# ADC-RDC-ADC.net
KiCad netlist of a schematic drawn in Altium Designer
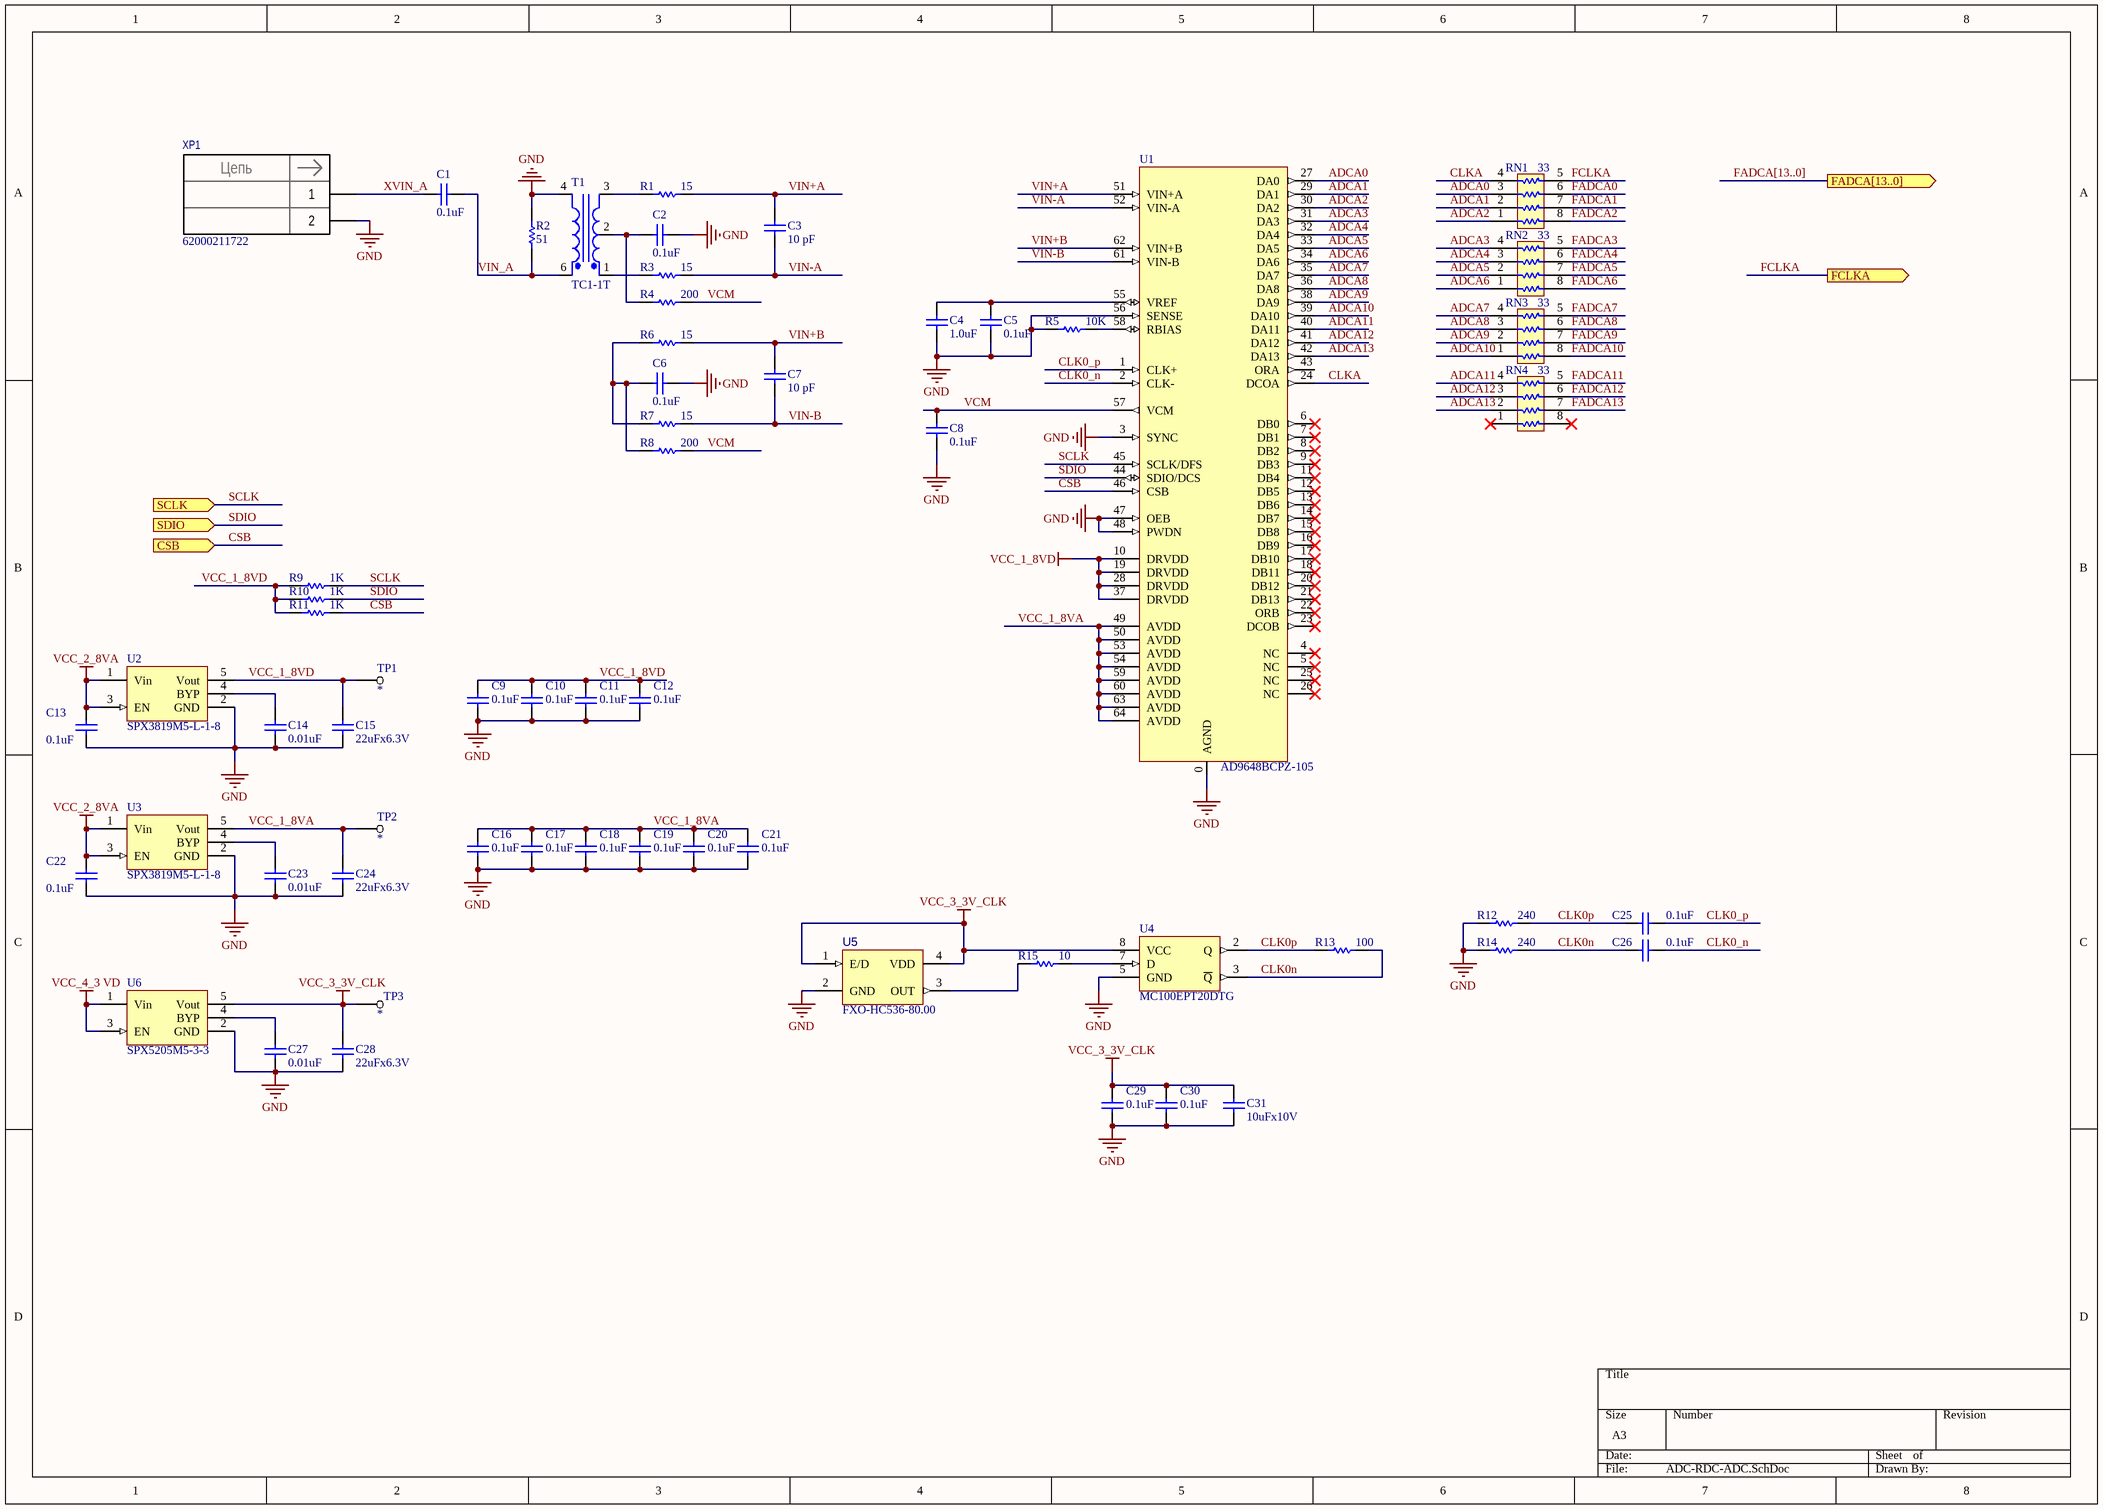
[diagram p0: ADC-RDC-ADC.SchDoc]

(export (version "E")
  (design (tool "Eeschema 10.0.6"))
  (components
    (comp (ref "C1")
      (value "0.1uF")
      (footprint "C0603")
      (description "Capacitor, 2pin")
      (libsource (lib "") (part "Cap_1"))
    )
    (comp (ref "C2")
      (value "0.1uF")
      (footprint "C0603")
      (description "Capacitor, 2pin")
      (libsource (lib "GC500EM2") (part "Cap"))
    )
    (comp (ref "C3")
      (value "10 pF")
      (footprint "C0603")
      (description "Capacitor, 2pin")
      (libsource (lib "GC500EM2") (part "Cap"))
    )
    (comp (ref "C4")
      (value "1.0uF")
      (footprint "C0603L")
      (description "Capacitor, 2pin")
      (libsource (lib "GC500EM2") (part "Cap"))
    )
    (comp (ref "C5")
      (value "0.1uF")
      (footprint "C0603L")
      (description "Capacitor, 2pin")
      (libsource (lib "GC500EM2") (part "Cap"))
    )
    (comp (ref "C6")
      (value "0.1uF")
      (footprint "C0603")
      (description "Capacitor, 2pin")
      (libsource (lib "GC500EM2") (part "Cap"))
    )
    (comp (ref "C7")
      (value "10 pF")
      (footprint "C0603")
      (description "Capacitor, 2pin")
      (libsource (lib "GC500EM2") (part "Cap"))
    )
    (comp (ref "C8")
      (value "0.1uF")
      (footprint "C0603L")
      (description "Capacitor, 2pin")
      (libsource (lib "GC500EM2") (part "Cap"))
    )
    (comp (ref "C9")
      (value "0.1uF")
      (footprint "C0603")
      (description "Capacitor, 2pin")
      (libsource (lib "GC500EM2") (part "Cap"))
    )
    (comp (ref "C10")
      (value "0.1uF")
      (footprint "C0603")
      (description "Capacitor, 2pin")
      (libsource (lib "GC500EM2") (part "Cap"))
    )
    (comp (ref "C11")
      (value "0.1uF")
      (footprint "C0603")
      (description "Capacitor, 2pin")
      (libsource (lib "GC500EM2") (part "Cap"))
    )
    (comp (ref "C12")
      (value "0.1uF")
      (footprint "C0603")
      (description "Capacitor, 2pin")
      (libsource (lib "GC500EM2") (part "Cap"))
    )
    (comp (ref "C13")
      (value "0.1uF")
      (footprint "C0603")
      (description "Capacitor, 2pin")
      (libsource (lib "GC500EM2") (part "Cap"))
    )
    (comp (ref "C14")
      (value "0.01uF")
      (footprint "C0603")
      (description "Capacitor, 2pin")
      (libsource (lib "GC500EM2") (part "Cap"))
    )
    (comp (ref "C15")
      (value "22uFx6.3V")
      (footprint "C0805")
      (description "Capacitor, 2pin")
      (libsource (lib "GC500EM2") (part "Cap"))
    )
    (comp (ref "C16")
      (value "0.1uF")
      (footprint "C0603L")
      (description "Capacitor, 2pin")
      (libsource (lib "GC500EM2") (part "Cap"))
    )
    (comp (ref "C17")
      (value "0.1uF")
      (footprint "C0603L")
      (description "Capacitor, 2pin")
      (libsource (lib "GC500EM2") (part "Cap"))
    )
    (comp (ref "C18")
      (value "0.1uF")
      (footprint "C0603L")
      (description "Capacitor, 2pin")
      (libsource (lib "GC500EM2") (part "Cap"))
    )
    (comp (ref "C19")
      (value "0.1uF")
      (footprint "C0603L")
      (description "Capacitor, 2pin")
      (libsource (lib "GC500EM2") (part "Cap"))
    )
    (comp (ref "C20")
      (value "0.1uF")
      (footprint "C0603L")
      (description "Capacitor, 2pin")
      (libsource (lib "GC500EM2") (part "Cap"))
    )
    (comp (ref "C21")
      (value "0.1uF")
      (footprint "C0603L")
      (description "Capacitor, 2pin")
      (libsource (lib "GC500EM2") (part "Cap"))
    )
    (comp (ref "C22")
      (value "0.1uF")
      (footprint "C0603")
      (description "Capacitor, 2pin")
      (libsource (lib "GC500EM2") (part "Cap"))
    )
    (comp (ref "C23")
      (value "0.01uF")
      (footprint "C0603")
      (description "Capacitor, 2pin")
      (libsource (lib "GC500EM2") (part "Cap"))
    )
    (comp (ref "C24")
      (value "22uFx6.3V")
      (footprint "C0805")
      (description "Capacitor, 2pin")
      (libsource (lib "GC500EM2") (part "Cap"))
    )
    (comp (ref "C25")
      (value "0.1uF")
      (footprint "C0603L")
      (description "Capacitor, 2pin")
      (libsource (lib "GC500EM2") (part "Cap"))
    )
    (comp (ref "C26")
      (value "0.1uF")
      (footprint "C0603L")
      (description "Capacitor, 2pin")
      (libsource (lib "GC500EM2") (part "Cap"))
    )
    (comp (ref "C27")
      (value "0.01uF")
      (footprint "C0603")
      (description "Capacitor, 2pin")
      (libsource (lib "GC500EM2") (part "Cap"))
    )
    (comp (ref "C28")
      (value "22uFx6.3V")
      (footprint "C0805")
      (description "Capacitor, 2pin")
      (libsource (lib "GC500EM2") (part "Cap"))
    )
    (comp (ref "C29")
      (value "0.1uF")
      (footprint "C0603")
      (description "Capacitor, 2pin")
      (libsource (lib "GC500EM2") (part "Cap"))
    )
    (comp (ref "C30")
      (value "0.1uF")
      (footprint "C0603")
      (description "Capacitor, 2pin")
      (libsource (lib "GC500EM2") (part "Cap"))
    )
    (comp (ref "C31")
      (value "10uFx10V")
      (footprint "C0805")
      (description "Capacitor, 2pin")
      (libsource (lib "GC500EM2") (part "Cap"))
    )
    (comp (ref "R1")
      (value "15")
      (footprint "R0603")
      (description "Resistor, 2pin")
      (libsource (lib "GC500EM2") (part "RES"))
    )
    (comp (ref "R2")
      (value "51")
      (footprint "R0805")
      (description "Resistor, 2pin")
      (libsource (lib "GC500EM2") (part "RES"))
    )
    (comp (ref "R3")
      (value "15")
      (footprint "R0603")
      (description "Resistor, 2pin")
      (libsource (lib "GC500EM2") (part "RES"))
    )
    (comp (ref "R4")
      (value "200")
      (footprint "R0603")
      (description "Resistor, 2pin")
      (libsource (lib "GC500EM2") (part "RES"))
    )
    (comp (ref "R5")
      (value "10K")
      (footprint "R0603L")
      (description "Resistor, 2pin")
      (libsource (lib "GC500EM2") (part "RES"))
    )
    (comp (ref "R6")
      (value "15")
      (footprint "R0603")
      (description "Resistor, 2pin")
      (libsource (lib "GC500EM2") (part "RES"))
    )
    (comp (ref "R7")
      (value "15")
      (footprint "R0603")
      (description "Resistor, 2pin")
      (libsource (lib "GC500EM2") (part "RES"))
    )
    (comp (ref "R8")
      (value "200")
      (footprint "R0603")
      (description "Resistor, 2pin")
      (libsource (lib "GC500EM2") (part "RES"))
    )
    (comp (ref "R9")
      (value "1K")
      (footprint "R0603")
      (description "Resistor, 2pin")
      (libsource (lib "GC500EM2") (part "RES"))
    )
    (comp (ref "R10")
      (value "1K")
      (footprint "R0603")
      (description "Resistor, 2pin")
      (libsource (lib "GC500EM2") (part "RES"))
    )
    (comp (ref "R11")
      (value "1K")
      (footprint "R0603")
      (description "Resistor, 2pin")
      (libsource (lib "GC500EM2") (part "RES"))
    )
    (comp (ref "R12")
      (value "240")
      (footprint "R0603")
      (description "Resistor, 2pin")
      (libsource (lib "GC500EM2") (part "RES"))
    )
    (comp (ref "R13")
      (value "100")
      (footprint "R0603")
      (description "Resistor, 2pin")
      (libsource (lib "GC500EM2") (part "RES"))
    )
    (comp (ref "R14")
      (value "240")
      (footprint "R0603")
      (description "Resistor, 2pin")
      (libsource (lib "GC500EM2") (part "RES"))
    )
    (comp (ref "R15")
      (value "10")
      (footprint "R0603")
      (description "Resistor, 2pin")
      (libsource (lib "GC500EM2") (part "RES"))
    )
    (comp (ref "RN1")
      (value "33")
      (footprint "EXB38V")
      (description "x4 Resistor Array")
      (libsource (lib "GC500EM2") (part "x4 Resistor Array"))
    )
    (comp (ref "RN2")
      (value "33")
      (footprint "EXB38V")
      (description "x4 Resistor Array")
      (libsource (lib "GC500EM2") (part "x4 Resistor Array"))
    )
    (comp (ref "RN3")
      (value "33")
      (footprint "EXB38V")
      (description "x4 Resistor Array")
      (libsource (lib "GC500EM2") (part "x4 Resistor Array"))
    )
    (comp (ref "RN4")
      (value "33")
      (footprint "EXB38V")
      (description "x4 Resistor Array")
      (libsource (lib "GC500EM2") (part "x4 Resistor Array"))
    )
    (comp (ref "T1")
      (value "TC1-1T")
      (footprint "SM-22")
      (description "Center-Tapped Transformer (Ideal)")
      (libsource (lib "GC500EM2") (part "TC1-1T"))
    )
    (comp (ref "TP1")
      (value "*")
      (footprint "TP_1_06")
      (description "Test point")
      (libsource (lib "GC500EM2") (part "Test_point"))
    )
    (comp (ref "TP2")
      (value "*")
      (footprint "TP_1_06")
      (description "Test point")
      (libsource (lib "GC500EM2") (part "Test_point"))
    )
    (comp (ref "TP3")
      (value "*")
      (footprint "TP_1_06")
      (description "Test point")
      (libsource (lib "GC500EM2") (part "Test_point"))
    )
    (comp (ref "U1")
      (value "AD9648BCPZ-105")
      (footprint "CP-64-4")
      (description "14-Bit, 125 MSPS/105 MSPS, 1.8 V Dual  Analog-to-Digital Converter")
      (libsource (lib "GC500EM2") (part "AD9648BCPZ-105"))
    )
    (comp (ref "U2")
      (value "SPX3819M5-L-1-8")
      (footprint "SOT23-5")
      (description "LDO Voltage Regulator")
      (libsource (lib "GC500EM2") (part "SPX3819M5-L-1-8"))
    )
    (comp (ref "U3")
      (value "SPX3819M5-L-1-8")
      (footprint "SOT23-5")
      (description "LDO Voltage Regulator")
      (libsource (lib "GC500EM2") (part "SPX3819M5-L-1-8"))
    )
    (comp (ref "U4")
      (value "MC100EPT20DTG")
      (footprint "TSSOP8")
      (description "3.3 V TTL/CMOS to differential PECL translator")
      (libsource (lib "GC500EM2") (part "MC100EPT20DT"))
    )
    (comp (ref "U5")
      (value "FXO-HC536-80.00")
      (footprint "HC5")
      (description "Surface Mount Crystal Oscillator")
      (libsource (lib "GC500EM2") (part "SG-636PTF-40.0000"))
    )
    (comp (ref "U6")
      (value "SPX5205M5-3-3")
      (footprint "SOT23-5")
      (description "LDO Voltage Regulator")
      (libsource (lib "GC500EM2") (part "SPX5205M5-3-3"))
    )
    (comp (ref "XP1")
      (value "plug_62000211722_WR-WTB_2pin_horiz")
      (footprint "conP_WR-WTB_62000211722-2pin_P2000_60x76x48_L")
      (description "2.00mm Male Horizontal Shrouded Header WR-WTB")
      (fields
        (field (name "COMPONENT_NAME") "62000211722")
        (field (name "MANUFACTURER") "\"Wurth Elektronik\"")
      )
      (libsource (lib "Electromechanics") (part "plug_62000211722_WR-WTB_2pin_horiz"))
    )
  )
  (nets
    (net (code "1") (name "/ADCA0") (class "Default")
      (node (ref "RN1") (pin "3") (pintype "passive"))
      (node (ref "U1") (pin "27") (pinfunction "DA0_27") (pintype "output"))
    )
    (net (code "2") (name "/ADCA1") (class "Default")
      (node (ref "RN1") (pin "2") (pintype "passive"))
      (node (ref "U1") (pin "29") (pinfunction "DA1_29") (pintype "output"))
    )
    (net (code "3") (name "/ADCA2") (class "Default")
      (node (ref "RN1") (pin "1") (pintype "passive"))
      (node (ref "U1") (pin "30") (pinfunction "DA2_30") (pintype "output"))
    )
    (net (code "4") (name "/ADCA3") (class "Default")
      (node (ref "RN2") (pin "4") (pintype "passive"))
      (node (ref "U1") (pin "31") (pinfunction "DA3_31") (pintype "output"))
    )
    (net (code "5") (name "/ADCA4") (class "Default")
      (node (ref "RN2") (pin "3") (pintype "passive"))
      (node (ref "U1") (pin "32") (pinfunction "DA4_32") (pintype "output"))
    )
    (net (code "6") (name "/ADCA5") (class "Default")
      (node (ref "RN2") (pin "2") (pintype "passive"))
      (node (ref "U1") (pin "33") (pinfunction "DA5_33") (pintype "output"))
    )
    (net (code "7") (name "/ADCA6") (class "Default")
      (node (ref "RN2") (pin "1") (pintype "passive"))
      (node (ref "U1") (pin "34") (pinfunction "DA6_34") (pintype "output"))
    )
    (net (code "8") (name "/ADCA7") (class "Default")
      (node (ref "RN3") (pin "4") (pintype "passive"))
      (node (ref "U1") (pin "35") (pinfunction "DA7_35") (pintype "output"))
    )
    (net (code "9") (name "/ADCA8") (class "Default")
      (node (ref "RN3") (pin "3") (pintype "passive"))
      (node (ref "U1") (pin "36") (pinfunction "DA8_36") (pintype "output"))
    )
    (net (code "10") (name "/ADCA9") (class "Default")
      (node (ref "RN3") (pin "2") (pintype "passive"))
      (node (ref "U1") (pin "38") (pinfunction "DA9_38") (pintype "output"))
    )
    (net (code "11") (name "/ADCA10") (class "Default")
      (node (ref "RN3") (pin "1") (pintype "passive"))
      (node (ref "U1") (pin "39") (pinfunction "DA10_39") (pintype "output"))
    )
    (net (code "12") (name "/ADCA11") (class "Default")
      (node (ref "RN4") (pin "4") (pintype "passive"))
      (node (ref "U1") (pin "40") (pinfunction "DA11_40") (pintype "output"))
    )
    (net (code "13") (name "/ADCA12") (class "Default")
      (node (ref "RN4") (pin "3") (pintype "passive"))
      (node (ref "U1") (pin "41") (pinfunction "DA12_41") (pintype "output"))
    )
    (net (code "14") (name "/ADCA13") (class "Default")
      (node (ref "RN4") (pin "2") (pintype "passive"))
      (node (ref "U1") (pin "42") (pinfunction "DA13_42") (pintype "output"))
    )
    (net (code "15") (name "/CLK0_n") (class "Default")
      (node (ref "C26") (pin "2") (pinfunction "2_2") (pintype "passive"))
      (node (ref "U1") (pin "2") (pinfunction "CLK-_2") (pintype "input"))
    )
    (net (code "16") (name "/CLK0_p") (class "Default")
      (node (ref "C25") (pin "2") (pinfunction "2_2") (pintype "passive"))
      (node (ref "U1") (pin "1") (pinfunction "CLK+_1") (pintype "input"))
    )
    (net (code "17") (name "/CLK0n") (class "Default")
      (node (ref "C26") (pin "1") (pinfunction "1_1") (pintype "passive"))
      (node (ref "R13") (pin "2") (pinfunction "2_2") (pintype "passive"))
      (node (ref "R14") (pin "2") (pinfunction "2_2") (pintype "passive"))
      (node (ref "U4") (pin "3") (pinfunction "~{Q}_3") (pintype "output"))
    )
    (net (code "18") (name "/CLK0p") (class "Default")
      (node (ref "C25") (pin "1") (pinfunction "1_1") (pintype "passive"))
      (node (ref "R12") (pin "2") (pinfunction "2_2") (pintype "passive"))
      (node (ref "R13") (pin "1") (pinfunction "1_1") (pintype "passive"))
      (node (ref "U4") (pin "2") (pinfunction "Q_2") (pintype "output"))
    )
    (net (code "19") (name "/CLKA") (class "Default")
      (node (ref "RN1") (pin "4") (pintype "passive"))
      (node (ref "U1") (pin "24") (pinfunction "DCOA_24") (pintype "output"))
    )
    (net (code "20") (name "/CSB") (class "Default")
      (node (ref "R11") (pin "2") (pinfunction "2_2") (pintype "passive"))
      (node (ref "U1") (pin "46") (pinfunction "CSB_46") (pintype "input"))
    )
    (net (code "21") (name "/FADCA0") (class "Default") (node (ref "RN1") (pin "6") (pintype "passive")))
    (net (code "22") (name "/FADCA1") (class "Default") (node (ref "RN1") (pin "7") (pintype "passive")))
    (net (code "23") (name "/FADCA2") (class "Default") (node (ref "RN1") (pin "8") (pintype "passive")))
    (net (code "24") (name "/FADCA3") (class "Default") (node (ref "RN2") (pin "5") (pintype "passive")))
    (net (code "25") (name "/FADCA4") (class "Default") (node (ref "RN2") (pin "6") (pintype "passive")))
    (net (code "26") (name "/FADCA5") (class "Default") (node (ref "RN2") (pin "7") (pintype "passive")))
    (net (code "27") (name "/FADCA6") (class "Default") (node (ref "RN2") (pin "8") (pintype "passive")))
    (net (code "28") (name "/FADCA7") (class "Default") (node (ref "RN3") (pin "5") (pintype "passive")))
    (net (code "29") (name "/FADCA8") (class "Default") (node (ref "RN3") (pin "6") (pintype "passive")))
    (net (code "30") (name "/FADCA9") (class "Default") (node (ref "RN3") (pin "7") (pintype "passive")))
    (net (code "31") (name "/FADCA10") (class "Default") (node (ref "RN3") (pin "8") (pintype "passive")))
    (net (code "32") (name "/FADCA11") (class "Default") (node (ref "RN4") (pin "5") (pintype "passive")))
    (net (code "33") (name "/FADCA12") (class "Default") (node (ref "RN4") (pin "6") (pintype "passive")))
    (net (code "34") (name "/FADCA13") (class "Default") (node (ref "RN4") (pin "7") (pintype "passive")))
    (net (code "36") (name "/FCLKA") (class "Default") (node (ref "RN1") (pin "5") (pintype "passive")))
    (net (code "37") (name "/SCLK") (class "Default")
      (node (ref "R9") (pin "2") (pinfunction "2_2") (pintype "passive"))
      (node (ref "U1") (pin "45") (pinfunction "SCLK/DFS_45") (pintype "input"))
    )
    (net (code "38") (name "/SDIO") (class "Default")
      (node (ref "R10") (pin "2") (pinfunction "2_2") (pintype "passive"))
      (node (ref "U1") (pin "44") (pinfunction "SDIO/DCS_44") (pintype "bidirectional"))
    )
    (net (code "39") (name "/VCC_1_8VA") (class "Default")
      (node (ref "C16") (pin "2") (pinfunction "2_2") (pintype "passive"))
      (node (ref "C17") (pin "2") (pinfunction "2_2") (pintype "passive"))
      (node (ref "C18") (pin "2") (pinfunction "2_2") (pintype "passive"))
      (node (ref "C19") (pin "2") (pinfunction "2_2") (pintype "passive"))
      (node (ref "C20") (pin "2") (pinfunction "2_2") (pintype "passive"))
      (node (ref "C21") (pin "2") (pinfunction "2_2") (pintype "passive"))
      (node (ref "C24") (pin "2") (pinfunction "2_2") (pintype "passive"))
      (node (ref "TP2") (pin "1") (pinfunction "1_1") (pintype "passive"))
      (node (ref "U1") (pin "49") (pinfunction "AVDD_49") (pintype "power_in"))
      (node (ref "U1") (pin "50") (pinfunction "AVDD_50") (pintype "power_in"))
      (node (ref "U1") (pin "53") (pinfunction "AVDD_53") (pintype "power_in"))
      (node (ref "U1") (pin "54") (pinfunction "AVDD_54") (pintype "power_in"))
      (node (ref "U1") (pin "59") (pinfunction "AVDD_59") (pintype "power_in"))
      (node (ref "U1") (pin "60") (pinfunction "AVDD_60") (pintype "power_in"))
      (node (ref "U1") (pin "63") (pinfunction "AVDD_63") (pintype "power_in"))
      (node (ref "U1") (pin "64") (pinfunction "AVDD_64") (pintype "power_in"))
      (node (ref "U3") (pin "5") (pinfunction "Vout_5") (pintype "passive"))
    )
    (net (code "40") (name "/VCM") (class "Default")
      (node (ref "C8") (pin "2") (pinfunction "2_2") (pintype "passive"))
      (node (ref "R4") (pin "2") (pinfunction "2_2") (pintype "passive"))
      (node (ref "R8") (pin "2") (pinfunction "2_2") (pintype "passive"))
      (node (ref "U1") (pin "57") (pinfunction "VCM_57") (pintype "output"))
    )
    (net (code "41") (name "/VIN+A") (class "Default")
      (node (ref "C3") (pin "1") (pinfunction "1_1") (pintype "passive"))
      (node (ref "R1") (pin "2") (pinfunction "2_2") (pintype "passive"))
      (node (ref "U1") (pin "51") (pinfunction "VIN+A_51") (pintype "input"))
    )
    (net (code "42") (name "/VIN+B") (class "Default")
      (node (ref "C7") (pin "1") (pinfunction "1_1") (pintype "passive"))
      (node (ref "R6") (pin "2") (pinfunction "2_2") (pintype "passive"))
      (node (ref "U1") (pin "62") (pinfunction "VIN+B_62") (pintype "input"))
    )
    (net (code "43") (name "/VIN-A") (class "Default")
      (node (ref "C3") (pin "2") (pinfunction "2_2") (pintype "passive"))
      (node (ref "R3") (pin "2") (pinfunction "2_2") (pintype "passive"))
      (node (ref "U1") (pin "52") (pinfunction "VIN-A_52") (pintype "input"))
    )
    (net (code "44") (name "/VIN-B") (class "Default")
      (node (ref "C7") (pin "2") (pinfunction "2_2") (pintype "passive"))
      (node (ref "R7") (pin "2") (pinfunction "2_2") (pintype "passive"))
      (node (ref "U1") (pin "61") (pinfunction "VIN-B_61") (pintype "input"))
    )
    (net (code "45") (name "/VIN_A") (class "Default")
      (node (ref "C1") (pin "1") (pinfunction "1_1") (pintype "passive"))
      (node (ref "R2") (pin "1") (pinfunction "1_1") (pintype "passive"))
      (node (ref "T1") (pin "6") (pinfunction "Pri+_6") (pintype "passive"))
    )
    (net (code "46") (name "/XVIN_A") (class "Default")
      (node (ref "C1") (pin "2") (pinfunction "2_2") (pintype "passive"))
      (node (ref "XP1") (pin "1") (pinfunction "1_1") (pintype "passive"))
    )
    (net (code "47") (name "GND") (class "Default")
      (node (ref "C10") (pin "1") (pinfunction "1_1") (pintype "passive"))
      (node (ref "C11") (pin "1") (pinfunction "1_1") (pintype "passive"))
      (node (ref "C12") (pin "1") (pinfunction "1_1") (pintype "passive"))
      (node (ref "C13") (pin "1") (pinfunction "1_1") (pintype "passive"))
      (node (ref "C14") (pin "1") (pinfunction "1_1") (pintype "passive"))
      (node (ref "C15") (pin "1") (pinfunction "1_1") (pintype "passive"))
      (node (ref "C16") (pin "1") (pinfunction "1_1") (pintype "passive"))
      (node (ref "C17") (pin "1") (pinfunction "1_1") (pintype "passive"))
      (node (ref "C18") (pin "1") (pinfunction "1_1") (pintype "passive"))
      (node (ref "C19") (pin "1") (pinfunction "1_1") (pintype "passive"))
      (node (ref "C2") (pin "2") (pinfunction "2_2") (pintype "passive"))
      (node (ref "C20") (pin "1") (pinfunction "1_1") (pintype "passive"))
      (node (ref "C21") (pin "1") (pinfunction "1_1") (pintype "passive"))
      (node (ref "C22") (pin "1") (pinfunction "1_1") (pintype "passive"))
      (node (ref "C23") (pin "1") (pinfunction "1_1") (pintype "passive"))
      (node (ref "C24") (pin "1") (pinfunction "1_1") (pintype "passive"))
      (node (ref "C27") (pin "1") (pinfunction "1_1") (pintype "passive"))
      (node (ref "C28") (pin "1") (pinfunction "1_1") (pintype "passive"))
      (node (ref "C29") (pin "1") (pinfunction "1_1") (pintype "passive"))
      (node (ref "C30") (pin "1") (pinfunction "1_1") (pintype "passive"))
      (node (ref "C31") (pin "1") (pinfunction "1_1") (pintype "passive"))
      (node (ref "C4") (pin "1") (pinfunction "1_1") (pintype "passive"))
      (node (ref "C5") (pin "1") (pinfunction "1_1") (pintype "passive"))
      (node (ref "C6") (pin "2") (pinfunction "2_2") (pintype "passive"))
      (node (ref "C8") (pin "1") (pinfunction "1_1") (pintype "passive"))
      (node (ref "C9") (pin "1") (pinfunction "1_1") (pintype "passive"))
      (node (ref "R12") (pin "1") (pinfunction "1_1") (pintype "passive"))
      (node (ref "R14") (pin "1") (pinfunction "1_1") (pintype "passive"))
      (node (ref "R2") (pin "2") (pinfunction "2_2") (pintype "passive"))
      (node (ref "R5") (pin "1") (pinfunction "1_1") (pintype "passive"))
      (node (ref "T1") (pin "4") (pinfunction "Pri-_4") (pintype "passive"))
      (node (ref "U1") (pin "0") (pinfunction "AGND_0") (pintype "power_in"))
      (node (ref "U1") (pin "3") (pinfunction "SYNC_3") (pintype "input"))
      (node (ref "U1") (pin "47") (pinfunction "OEB_47") (pintype "input"))
      (node (ref "U1") (pin "48") (pinfunction "PWDN_48") (pintype "input"))
      (node (ref "U1") (pin "56") (pinfunction "SENSE_56") (pintype "input"))
      (node (ref "U2") (pin "2") (pinfunction "GND_2") (pintype "passive"))
      (node (ref "U3") (pin "2") (pinfunction "GND_2") (pintype "passive"))
      (node (ref "U4") (pin "5") (pinfunction "GND_5") (pintype "power_in"))
      (node (ref "U5") (pin "2") (pinfunction "GND_2") (pintype "power_in"))
      (node (ref "U6") (pin "2") (pinfunction "GND_2") (pintype "passive"))
      (node (ref "XP1") (pin "2") (pinfunction "2_2") (pintype "passive"))
    )
    (net (code "48") (name "Net-(C6-Pad1)") (class "Default")
      (node (ref "C6") (pin "1") (pinfunction "1_1") (pintype "passive"))
      (node (ref "R6") (pin "1") (pinfunction "1_1") (pintype "passive"))
      (node (ref "R7") (pin "1") (pinfunction "1_1") (pintype "passive"))
      (node (ref "R8") (pin "1") (pinfunction "1_1") (pintype "passive"))
    )
    (net (code "49") (name "Net-(T1-Sec+)") (class "Default")
      (node (ref "R3") (pin "1") (pinfunction "1_1") (pintype "passive"))
      (node (ref "T1") (pin "1") (pinfunction "Sec+_1") (pintype "passive"))
    )
    (net (code "50") (name "Net-(T1-Sec-)") (class "Default")
      (node (ref "R1") (pin "1") (pinfunction "1_1") (pintype "passive"))
      (node (ref "T1") (pin "3") (pinfunction "Sec-_3") (pintype "passive"))
    )
    (net (code "51") (name "Net-(T1-SecCT)") (class "Default")
      (node (ref "C2") (pin "1") (pinfunction "1_1") (pintype "passive"))
      (node (ref "R4") (pin "1") (pinfunction "1_1") (pintype "passive"))
      (node (ref "T1") (pin "2") (pinfunction "SecCT_2") (pintype "passive"))
    )
    (net (code "52") (name "Net-(U1-RBIAS)") (class "Default")
      (node (ref "R5") (pin "2") (pinfunction "2_2") (pintype "passive"))
      (node (ref "U1") (pin "58") (pinfunction "RBIAS_58") (pintype "bidirectional"))
    )
    (net (code "53") (name "Net-(U1-VREF)") (class "Default")
      (node (ref "C4") (pin "2") (pinfunction "2_2") (pintype "passive"))
      (node (ref "C5") (pin "2") (pinfunction "2_2") (pintype "passive"))
      (node (ref "U1") (pin "55") (pinfunction "VREF_55") (pintype "bidirectional"))
    )
    (net (code "54") (name "Net-(U2-BYP)") (class "Default")
      (node (ref "C14") (pin "2") (pinfunction "2_2") (pintype "passive"))
      (node (ref "U2") (pin "4") (pinfunction "BYP_4") (pintype "passive"))
    )
    (net (code "55") (name "Net-(U3-BYP)") (class "Default")
      (node (ref "C23") (pin "2") (pinfunction "2_2") (pintype "passive"))
      (node (ref "U3") (pin "4") (pinfunction "BYP_4") (pintype "passive"))
    )
    (net (code "56") (name "Net-(U4-D)") (class "Default")
      (node (ref "R15") (pin "2") (pinfunction "2_2") (pintype "passive"))
      (node (ref "U4") (pin "7") (pinfunction "D_7") (pintype "input"))
    )
    (net (code "57") (name "Net-(U5-OUT)") (class "Default")
      (node (ref "R15") (pin "1") (pinfunction "1_1") (pintype "passive"))
      (node (ref "U5") (pin "3") (pinfunction "OUT_3") (pintype "output"))
    )
    (net (code "58") (name "Net-(U6-BYP)") (class "Default")
      (node (ref "C27") (pin "2") (pinfunction "2_2") (pintype "passive"))
      (node (ref "U6") (pin "4") (pinfunction "BYP_4") (pintype "passive"))
    )
    (net (code "59") (name "VCC_1_8VD") (class "Default")
      (node (ref "C10") (pin "2") (pinfunction "2_2") (pintype "passive"))
      (node (ref "C11") (pin "2") (pinfunction "2_2") (pintype "passive"))
      (node (ref "C12") (pin "2") (pinfunction "2_2") (pintype "passive"))
      (node (ref "C15") (pin "2") (pinfunction "2_2") (pintype "passive"))
      (node (ref "C9") (pin "2") (pinfunction "2_2") (pintype "passive"))
      (node (ref "R10") (pin "1") (pinfunction "1_1") (pintype "passive"))
      (node (ref "R11") (pin "1") (pinfunction "1_1") (pintype "passive"))
      (node (ref "R9") (pin "1") (pinfunction "1_1") (pintype "passive"))
      (node (ref "TP1") (pin "1") (pinfunction "1_1") (pintype "passive"))
      (node (ref "U1") (pin "10") (pinfunction "DRVDD_10") (pintype "power_in"))
      (node (ref "U1") (pin "19") (pinfunction "DRVDD_19") (pintype "power_in"))
      (node (ref "U1") (pin "28") (pinfunction "DRVDD_28") (pintype "power_in"))
      (node (ref "U1") (pin "37") (pinfunction "DRVDD_37") (pintype "power_in"))
      (node (ref "U2") (pin "5") (pinfunction "Vout_5") (pintype "passive"))
    )
    (net (code "60") (name "VCC_2_8VA") (class "Default")
      (node (ref "C13") (pin "2") (pinfunction "2_2") (pintype "passive"))
      (node (ref "C22") (pin "2") (pinfunction "2_2") (pintype "passive"))
      (node (ref "U2") (pin "1") (pinfunction "Vin_1") (pintype "passive"))
      (node (ref "U2") (pin "3") (pinfunction "EN_3") (pintype "input"))
      (node (ref "U3") (pin "1") (pinfunction "Vin_1") (pintype "passive"))
      (node (ref "U3") (pin "3") (pinfunction "EN_3") (pintype "input"))
    )
    (net (code "61") (name "VCC_3_3V_CLK") (class "Default")
      (node (ref "C28") (pin "2") (pinfunction "2_2") (pintype "passive"))
      (node (ref "C29") (pin "2") (pinfunction "2_2") (pintype "passive"))
      (node (ref "C30") (pin "2") (pinfunction "2_2") (pintype "passive"))
      (node (ref "C31") (pin "2") (pinfunction "2_2") (pintype "passive"))
      (node (ref "TP3") (pin "1") (pinfunction "1_1") (pintype "passive"))
      (node (ref "U4") (pin "8") (pinfunction "VCC_8") (pintype "passive"))
      (node (ref "U5") (pin "1") (pinfunction "E/D_1") (pintype "input"))
      (node (ref "U5") (pin "4") (pinfunction "VDD_4") (pintype "power_in"))
      (node (ref "U6") (pin "5") (pinfunction "Vout_5") (pintype "passive"))
    )
    (net (code "62") (name "VCC_4_3 VD") (class "Default")
      (node (ref "U6") (pin "1") (pinfunction "Vin_1") (pintype "passive"))
      (node (ref "U6") (pin "3") (pinfunction "EN_3") (pintype "input"))
    )
    (net (code "63") (name "unconnected-(RN4-Pad1)") (class "Default")
      (node (ref "RN4") (pin "1") (pintype "passive+no_connect"))
    )
    (net (code "64") (name "unconnected-(RN4-Pad8)") (class "Default")
      (node (ref "RN4") (pin "8") (pintype "passive+no_connect"))
    )
    (net (code "65") (name "unconnected-(U1-DB0-Pad6)") (class "Default")
      (node (ref "U1") (pin "6") (pinfunction "DB0_6") (pintype "output+no_connect"))
    )
    (net (code "66") (name "unconnected-(U1-DB1-Pad7)") (class "Default")
      (node (ref "U1") (pin "7") (pinfunction "DB1_7") (pintype "output+no_connect"))
    )
    (net (code "67") (name "unconnected-(U1-DB2-Pad8)") (class "Default")
      (node (ref "U1") (pin "8") (pinfunction "DB2_8") (pintype "output+no_connect"))
    )
    (net (code "68") (name "unconnected-(U1-DB3-Pad9)") (class "Default")
      (node (ref "U1") (pin "9") (pinfunction "DB3_9") (pintype "output+no_connect"))
    )
    (net (code "69") (name "unconnected-(U1-DB4-Pad11)") (class "Default")
      (node (ref "U1") (pin "11") (pinfunction "DB4_11") (pintype "output+no_connect"))
    )
    (net (code "70") (name "unconnected-(U1-DB5-Pad12)") (class "Default")
      (node (ref "U1") (pin "12") (pinfunction "DB5_12") (pintype "output+no_connect"))
    )
    (net (code "71") (name "unconnected-(U1-DB6-Pad13)") (class "Default")
      (node (ref "U1") (pin "13") (pinfunction "DB6_13") (pintype "output+no_connect"))
    )
    (net (code "72") (name "unconnected-(U1-DB7-Pad14)") (class "Default")
      (node (ref "U1") (pin "14") (pinfunction "DB7_14") (pintype "output+no_connect"))
    )
    (net (code "73") (name "unconnected-(U1-DB8-Pad15)") (class "Default")
      (node (ref "U1") (pin "15") (pinfunction "DB8_15") (pintype "output+no_connect"))
    )
    (net (code "74") (name "unconnected-(U1-DB9-Pad16)") (class "Default")
      (node (ref "U1") (pin "16") (pinfunction "DB9_16") (pintype "output+no_connect"))
    )
    (net (code "75") (name "unconnected-(U1-DB10-Pad17)") (class "Default")
      (node (ref "U1") (pin "17") (pinfunction "DB10_17") (pintype "output+no_connect"))
    )
    (net (code "76") (name "unconnected-(U1-DB11-Pad18)") (class "Default")
      (node (ref "U1") (pin "18") (pinfunction "DB11_18") (pintype "output+no_connect"))
    )
    (net (code "77") (name "unconnected-(U1-DB12-Pad20)") (class "Default")
      (node (ref "U1") (pin "20") (pinfunction "DB12_20") (pintype "output+no_connect"))
    )
    (net (code "78") (name "unconnected-(U1-DB13-Pad21)") (class "Default")
      (node (ref "U1") (pin "21") (pinfunction "DB13_21") (pintype "output+no_connect"))
    )
    (net (code "79") (name "unconnected-(U1-DCOB-Pad23)") (class "Default")
      (node (ref "U1") (pin "23") (pinfunction "DCOB_23") (pintype "output+no_connect"))
    )
    (net (code "80") (name "unconnected-(U1-NC-Pad4)") (class "Default")
      (node (ref "U1") (pin "4") (pinfunction "NC_4") (pintype "passive+no_connect"))
    )
    (net (code "81") (name "unconnected-(U1-NC-Pad5)") (class "Default")
      (node (ref "U1") (pin "5") (pinfunction "NC_5") (pintype "passive+no_connect"))
    )
    (net (code "82") (name "unconnected-(U1-NC-Pad25)") (class "Default")
      (node (ref "U1") (pin "25") (pinfunction "NC_25") (pintype "passive+no_connect"))
    )
    (net (code "83") (name "unconnected-(U1-NC-Pad26)") (class "Default")
      (node (ref "U1") (pin "26") (pinfunction "NC_26") (pintype "passive+no_connect"))
    )
    (net (code "84") (name "unconnected-(U1-ORA-Pad43)") (class "Default")
      (node (ref "U1") (pin "43") (pinfunction "ORA_43") (pintype "output"))
    )
    (net (code "85") (name "unconnected-(U1-ORB-Pad22)") (class "Default")
      (node (ref "U1") (pin "22") (pinfunction "ORB_22") (pintype "output+no_connect"))
    )
  )
)
